# Freezer-Monitor-v2-PCB.net
KiCad netlist of a schematic drawn in EAGLE
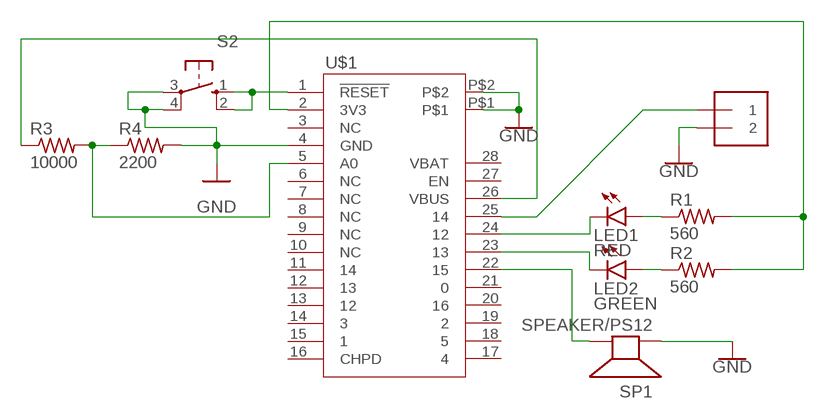
[diagram p0: schematic, sheet 1]

(export (version "E")
  (design (tool "Eeschema 10.0.6"))
  (components
    (comp (ref "J1")
      (value "1X2-3.5MM")
      (footprint "eagle-import:1X2-3.5MM")
      (libsource (lib "eagle-import") (part "1X2-3.5MM"))
    )
    (comp (ref "LED1")
      (value "RED")
      (footprint "eagle-import:LED10MM")
      (libsource (lib "eagle-import") (part "LED10MM"))
    )
    (comp (ref "LED2")
      (value "GREEN")
      (footprint "eagle-import:LED10MM")
      (libsource (lib "eagle-import") (part "LED10MM"))
    )
    (comp (ref "R1")
      (value "560")
      (footprint "eagle-import:0207_9")
      (libsource (lib "eagle-import") (part "adafruit_420_R-US_0207/9"))
    )
    (comp (ref "R2")
      (value "560")
      (footprint "eagle-import:0207_9")
      (libsource (lib "eagle-import") (part "adafruit_420_R-US_0207/9"))
    )
    (comp (ref "R3")
      (value "10000")
      (footprint "eagle-import:0207_9")
      (libsource (lib "eagle-import") (part "R-US_0207/9"))
    )
    (comp (ref "R4")
      (value "2200")
      (footprint "eagle-import:0207_9")
      (libsource (lib "eagle-import") (part "R-US_0207/9"))
    )
    (comp (ref "S2")
      (value "10-XX")
      (footprint "eagle-import:B3F-10XX")
      (fields (field (name "MPN") "B3F-1000"))
      (libsource (lib "eagle-import") (part "10-XX"))
    )
    (comp (ref "SP1")
      (value "SPEAKER/PS12")
      (footprint "eagle-import:PS12")
      (libsource (lib "eagle-import") (part "SPEAKER/PS12"))
    )
    (comp (ref "U$1")
      (value "FEATHER_ESP8266_HUZZAHFEATHER_HUZZAH")
      (footprint "eagle-import:FEATHER")
      (libsource (lib "eagle-import") (part "FEATHER_ESP8266_HUZZAHFEATHER_HUZZAH"))
    )
  )
  (nets
    (net (code "1") (name "/VBAT") (class "Default")
      (node (ref "U$1") (pin "28") (pinfunction "VBAT_28") (pintype "power_in"))
    )
    (net (code "2") (name "GND") (class "Default")
      (node (ref "J1") (pin "2") (pinfunction "2_2") (pintype "passive"))
      (node (ref "R4") (pin "2") (pinfunction "2_2") (pintype "passive"))
      (node (ref "S2") (pin "3") (pinfunction "P_3") (pintype "passive"))
      (node (ref "S2") (pin "4") (pinfunction "P1_4") (pintype "passive"))
      (node (ref "SP1") (pin "P$1") (pinfunction "+_P$1") (pintype "passive"))
      (node (ref "U$1") (pin "4") (pinfunction "GND_4") (pintype "power_in"))
      (node (ref "U$1") (pin "P$1") (pinfunction "P$1_P$1") (pintype "power_in"))
      (node (ref "U$1") (pin "P$2") (pinfunction "P$2_P$2") (pintype "power_in"))
    )
    (net (code "3") (name "Net-(J1-Pad1)") (class "Default")
      (node (ref "J1") (pin "1") (pinfunction "1_1") (pintype "passive"))
      (node (ref "U$1") (pin "25") (pinfunction "14_25") (pintype "bidirectional"))
    )
    (net (code "4") (name "Net-(LED1-C)") (class "Default")
      (node (ref "LED1") (pin "K") (pinfunction "C_K") (pintype "passive"))
      (node (ref "U$1") (pin "24") (pinfunction "12_24") (pintype "bidirectional"))
    )
    (net (code "5") (name "Net-(LED1-PadA)") (class "Default")
      (node (ref "LED1") (pin "A") (pinfunction "A_A") (pintype "passive"))
      (node (ref "R1") (pin "1") (pinfunction "1_1") (pintype "passive"))
    )
    (net (code "6") (name "Net-(LED2-C)") (class "Default")
      (node (ref "LED2") (pin "K") (pinfunction "C_K") (pintype "passive"))
      (node (ref "U$1") (pin "23") (pinfunction "13_23") (pintype "bidirectional"))
    )
    (net (code "7") (name "Net-(LED2-PadA)") (class "Default")
      (node (ref "LED2") (pin "A") (pinfunction "A_A") (pintype "passive"))
      (node (ref "R2") (pin "1") (pinfunction "1_1") (pintype "passive"))
    )
    (net (code "8") (name "Net-(S2-S)") (class "Default")
      (node (ref "S2") (pin "1") (pinfunction "S_1") (pintype "passive"))
      (node (ref "S2") (pin "2") (pinfunction "S1_2") (pintype "passive"))
      (node (ref "U$1") (pin "1") (pinfunction "~{RESET}_1") (pintype "input"))
    )
    (net (code "9") (name "Net-(SP1--)") (class "Default")
      (node (ref "SP1") (pin "P$2") (pinfunction "-_P$2") (pintype "passive"))
      (node (ref "U$1") (pin "22") (pinfunction "15_22") (pintype "bidirectional"))
    )
    (net (code "10") (name "Net-(U$1-3V3)") (class "Default")
      (node (ref "R1") (pin "2") (pinfunction "2_2") (pintype "passive"))
      (node (ref "R2") (pin "2") (pinfunction "2_2") (pintype "passive"))
      (node (ref "U$1") (pin "2") (pinfunction "3V3_2") (pintype "power_in"))
    )
    (net (code "11") (name "Net-(U$1-A0)") (class "Default")
      (node (ref "R3") (pin "2") (pinfunction "2_2") (pintype "passive"))
      (node (ref "R4") (pin "1") (pinfunction "1_1") (pintype "passive"))
      (node (ref "U$1") (pin "5") (pinfunction "A0_5") (pintype "bidirectional"))
    )
    (net (code "12") (name "Net-(U$1-VBUS)") (class "Default")
      (node (ref "R3") (pin "1") (pinfunction "1_1") (pintype "passive"))
      (node (ref "U$1") (pin "26") (pinfunction "VBUS_26") (pintype "power_in"))
    )
    (net (code "13") (name "unconnected-(U$1-0-Pad21)") (class "Default")
      (node (ref "U$1") (pin "21") (pinfunction "0_21") (pintype "bidirectional"))
    )
    (net (code "14") (name "unconnected-(U$1-1-Pad15)") (class "Default")
      (node (ref "U$1") (pin "15") (pinfunction "1_15") (pintype "bidirectional"))
    )
    (net (code "15") (name "unconnected-(U$1-2-Pad19)") (class "Default")
      (node (ref "U$1") (pin "19") (pinfunction "2_19") (pintype "bidirectional"))
    )
    (net (code "16") (name "unconnected-(U$1-3-Pad14)") (class "Default")
      (node (ref "U$1") (pin "14") (pinfunction "3_14") (pintype "bidirectional"))
    )
    (net (code "17") (name "unconnected-(U$1-4-Pad17)") (class "Default")
      (node (ref "U$1") (pin "17") (pinfunction "4_17") (pintype "bidirectional"))
    )
    (net (code "18") (name "unconnected-(U$1-5-Pad18)") (class "Default")
      (node (ref "U$1") (pin "18") (pinfunction "5_18") (pintype "bidirectional"))
    )
    (net (code "19") (name "unconnected-(U$1-12-Pad13)") (class "Default")
      (node (ref "U$1") (pin "13") (pinfunction "12_13") (pintype "bidirectional"))
    )
    (net (code "20") (name "unconnected-(U$1-13-Pad12)") (class "Default")
      (node (ref "U$1") (pin "12") (pinfunction "13_12") (pintype "bidirectional"))
    )
    (net (code "21") (name "unconnected-(U$1-14-Pad11)") (class "Default")
      (node (ref "U$1") (pin "11") (pinfunction "14_11") (pintype "bidirectional"))
    )
    (net (code "22") (name "unconnected-(U$1-16-Pad20)") (class "Default")
      (node (ref "U$1") (pin "20") (pinfunction "16_20") (pintype "bidirectional"))
    )
    (net (code "23") (name "unconnected-(U$1-CHPD-Pad16)") (class "Default")
      (node (ref "U$1") (pin "16") (pinfunction "CHPD_16") (pintype "bidirectional"))
    )
    (net (code "24") (name "unconnected-(U$1-EN-Pad27)") (class "Default")
      (node (ref "U$1") (pin "27") (pinfunction "EN_27") (pintype "input"))
    )
    (net (code "25") (name "unconnected-(U$1-NC-Pad3)") (class "Default")
      (node (ref "U$1") (pin "3") (pinfunction "NC_3") (pintype "no_connect"))
    )
    (net (code "26") (name "unconnected-(U$1-NC-Pad6)") (class "Default")
      (node (ref "U$1") (pin "6") (pinfunction "NC_6") (pintype "no_connect"))
    )
    (net (code "27") (name "unconnected-(U$1-NC-Pad7)") (class "Default")
      (node (ref "U$1") (pin "7") (pinfunction "NC_7") (pintype "no_connect"))
    )
    (net (code "28") (name "unconnected-(U$1-NC-Pad8)") (class "Default")
      (node (ref "U$1") (pin "8") (pinfunction "NC_8") (pintype "no_connect"))
    )
    (net (code "29") (name "unconnected-(U$1-NC-Pad9)") (class "Default")
      (node (ref "U$1") (pin "9") (pinfunction "NC_9") (pintype "no_connect"))
    )
    (net (code "30") (name "unconnected-(U$1-NC-Pad10)") (class "Default")
      (node (ref "U$1") (pin "10") (pinfunction "NC_10") (pintype "no_connect"))
    )
  )
)
